# ECE_312_LAB_-_Diode_Temperture_Sensor.net
KiCad netlist of a schematic drawn in EAGLE
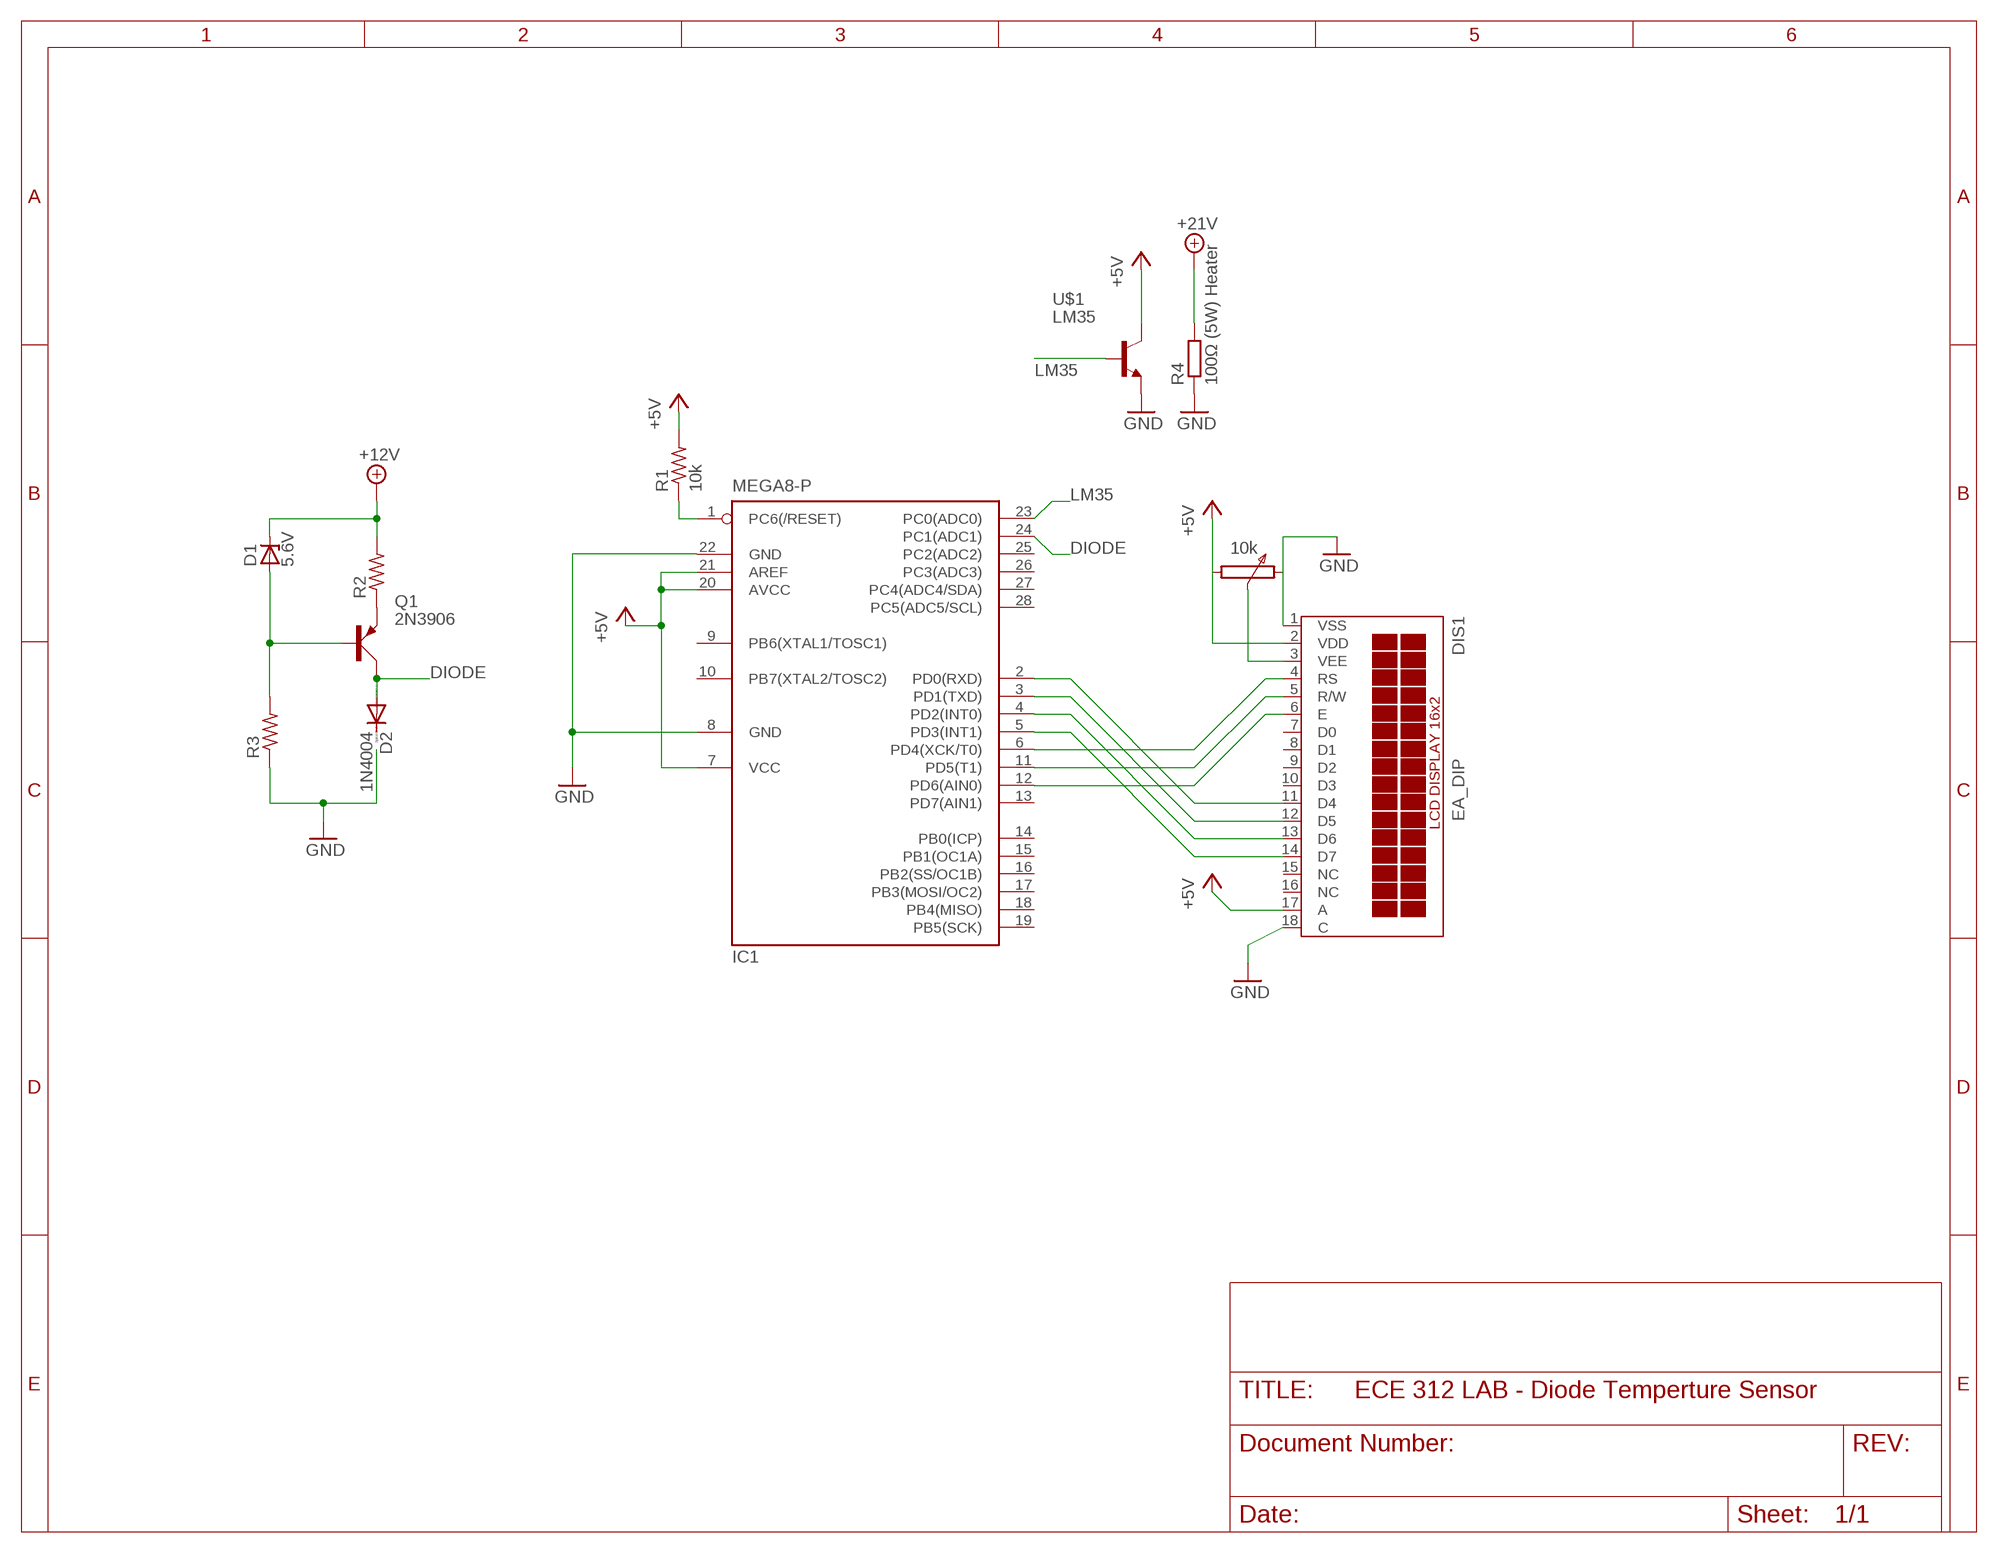
[diagram p0: schematic, sheet 1]

(export (version "E")
  (design (tool "Eeschema 10.0.6"))
  (components
    (comp (ref "D1")
      (value "5.6V")
      (footprint "eagle-import:C1702-15")
      (libsource (lib "eagle-import") (part "ZENER-DIODEC1702-15"))
    )
    (comp (ref "D2")
      (value "1N4004")
      (footprint "eagle-import:DO41-10")
      (libsource (lib "eagle-import") (part "1N4004"))
    )
    (comp (ref "DIS1")
      (value "EA_DIP")
      (footprint "eagle-import:EA_DIP")
      (libsource (lib "eagle-import") (part "EA_DIP"))
    )
    (comp (ref "IC1")
      (value "MEGA8-P")
      (footprint "eagle-import:DIL28-3")
      (libsource (lib "eagle-import") (part "MEGA8-P"))
    )
    (comp (ref "Q1")
      (value "2N3906")
      (footprint "eagle-import:TO92D")
      (libsource (lib "eagle-import") (part "2N3906"))
    )
    (comp (ref "R1")
      (value "10k")
      (footprint "eagle-import:0204V")
      (libsource (lib "eagle-import") (part "R-US_0204/2V"))
    )
    (comp (ref "R2")
      (value "R-US_0204/2V")
      (footprint "eagle-import:0204V")
      (libsource (lib "eagle-import") (part "R-US_0204/2V"))
    )
    (comp (ref "R3")
      (value "R-US_0204/2V")
      (footprint "eagle-import:0204V")
      (libsource (lib "eagle-import") (part "R-US_0204/2V"))
    )
    (comp (ref "R4")
      (value "100Ω (5W) Heater")
      (footprint "eagle-import:0204V")
      (libsource (lib "eagle-import") (part "R-EU_0204/2V"))
    )
    (comp (ref "U$1")
      (value "LM35")
      (footprint "eagle-import:TO220")
      (libsource (lib "eagle-import") (part "LM35"))
    )
  )
  (nets
    (net (code "1") (name "+5V") (class "Default")
      (node (ref "DIS1") (pin "17") (pinfunction "A_17") (pintype "passive"))
      (node (ref "DIS1") (pin "2") (pinfunction "VDD_2") (pintype "power_in"))
      (node (ref "IC1") (pin "20") (pinfunction "AVCC_20") (pintype "power_in"))
      (node (ref "IC1") (pin "21") (pinfunction "AREF_21") (pintype "passive"))
      (node (ref "IC1") (pin "7") (pinfunction "VCC_7") (pintype "power_in"))
      (node (ref "R1") (pin "2") (pinfunction "2_2") (pintype "passive"))
      (node (ref "U$1") (pin "2") (pinfunction "C_2") (pintype "passive"))
    )
    (net (code "2") (name "+12V") (class "Default")
      (node (ref "D1") (pin "C") (pinfunction "C_C") (pintype "passive"))
      (node (ref "R2") (pin "2") (pinfunction "2_2") (pintype "passive"))
    )
    (net (code "3") (name "+21V") (class "Default")
      (node (ref "R4") (pin "2") (pinfunction "2_2") (pintype "passive"))
    )
    (net (code "4") (name "/DIODE") (class "Default")
      (node (ref "D2") (pin "A") (pinfunction "A_A") (pintype "passive"))
      (node (ref "IC1") (pin "24") (pinfunction "PC1(ADC1)_24") (pintype "bidirectional"))
      (node (ref "Q1") (pin "C") (pinfunction "C_C") (pintype "passive"))
    )
    (net (code "5") (name "/LM35") (class "Default")
      (node (ref "IC1") (pin "23") (pinfunction "PC0(ADC0)_23") (pintype "bidirectional"))
      (node (ref "U$1") (pin "1") (pinfunction "B_1") (pintype "passive"))
    )
    (net (code "6") (name "GND") (class "Default")
      (node (ref "DIS1") (pin "1") (pinfunction "VSS_1") (pintype "power_in"))
      (node (ref "DIS1") (pin "18") (pinfunction "C_18") (pintype "passive"))
      (node (ref "IC1") (pin "22") (pinfunction "GND_22") (pintype "power_in"))
      (node (ref "IC1") (pin "8") (pinfunction "GND_8") (pintype "power_in"))
      (node (ref "R3") (pin "1") (pinfunction "1_1") (pintype "passive"))
      (node (ref "R4") (pin "1") (pinfunction "1_1") (pintype "passive"))
      (node (ref "U$1") (pin "3") (pinfunction "E_3") (pintype "passive"))
    )
    (net (code "7") (name "Net-(D1-PadA)") (class "Default")
      (node (ref "D1") (pin "A") (pinfunction "A_A") (pintype "passive"))
      (node (ref "Q1") (pin "B") (pinfunction "B_B") (pintype "passive"))
      (node (ref "R3") (pin "2") (pinfunction "2_2") (pintype "passive"))
    )
    (net (code "8") (name "Net-(DIS1-D4)") (class "Default")
      (node (ref "DIS1") (pin "11") (pinfunction "D4_11") (pintype "input"))
      (node (ref "IC1") (pin "2") (pinfunction "PD0(RXD)_2") (pintype "bidirectional"))
    )
    (net (code "9") (name "Net-(DIS1-D5)") (class "Default")
      (node (ref "DIS1") (pin "12") (pinfunction "D5_12") (pintype "input"))
      (node (ref "IC1") (pin "3") (pinfunction "PD1(TXD)_3") (pintype "bidirectional"))
    )
    (net (code "10") (name "Net-(DIS1-D6)") (class "Default")
      (node (ref "DIS1") (pin "13") (pinfunction "D6_13") (pintype "input"))
      (node (ref "IC1") (pin "4") (pinfunction "PD2(INT0)_4") (pintype "bidirectional"))
    )
    (net (code "11") (name "Net-(DIS1-D7)") (class "Default")
      (node (ref "DIS1") (pin "14") (pinfunction "D7_14") (pintype "input"))
      (node (ref "IC1") (pin "5") (pinfunction "PD3(INT1)_5") (pintype "bidirectional"))
    )
    (net (code "12") (name "Net-(DIS1-E)") (class "Default")
      (node (ref "DIS1") (pin "6") (pinfunction "E_6") (pintype "input"))
      (node (ref "IC1") (pin "12") (pinfunction "PD6(AIN0)_12") (pintype "bidirectional"))
    )
    (net (code "13") (name "Net-(DIS1-RS)") (class "Default")
      (node (ref "DIS1") (pin "4") (pinfunction "RS_4") (pintype "input"))
      (node (ref "IC1") (pin "6") (pinfunction "PD4(XCK/T0)_6") (pintype "bidirectional"))
    )
    (net (code "14") (name "Net-(DIS1-R{slash}W)") (class "Default")
      (node (ref "DIS1") (pin "5") (pinfunction "R/W_5") (pintype "input"))
      (node (ref "IC1") (pin "11") (pinfunction "PD5(T1)_11") (pintype "bidirectional"))
    )
    (net (code "15") (name "Net-(IC1-PC6({slash}RESET))") (class "Default")
      (node (ref "IC1") (pin "1") (pinfunction "PC6(/RESET)_1") (pintype "bidirectional"))
      (node (ref "R1") (pin "1") (pinfunction "1_1") (pintype "passive"))
    )
    (net (code "16") (name "Net-(Q1-PadE)") (class "Default")
      (node (ref "Q1") (pin "E") (pinfunction "E_E") (pintype "passive"))
      (node (ref "R2") (pin "1") (pinfunction "1_1") (pintype "passive"))
    )
    (net (code "17") (name "unconnected-(D2-PadC)") (class "Default")
      (node (ref "D2") (pin "C") (pinfunction "C_C") (pintype "passive"))
    )
    (net (code "18") (name "unconnected-(DIS1-D0-Pad7)") (class "Default")
      (node (ref "DIS1") (pin "7") (pinfunction "D0_7") (pintype "input"))
    )
    (net (code "19") (name "unconnected-(DIS1-D1-Pad8)") (class "Default")
      (node (ref "DIS1") (pin "8") (pinfunction "D1_8") (pintype "input"))
    )
    (net (code "20") (name "unconnected-(DIS1-D2-Pad9)") (class "Default")
      (node (ref "DIS1") (pin "9") (pinfunction "D2_9") (pintype "input"))
    )
    (net (code "21") (name "unconnected-(DIS1-D3-Pad10)") (class "Default")
      (node (ref "DIS1") (pin "10") (pinfunction "D3_10") (pintype "input"))
    )
    (net (code "22") (name "unconnected-(DIS1-NC-Pad15)") (class "Default")
      (node (ref "DIS1") (pin "15") (pinfunction "NC_15") (pintype "no_connect"))
    )
    (net (code "23") (name "unconnected-(DIS1-NC-Pad16)") (class "Default")
      (node (ref "DIS1") (pin "16") (pinfunction "NC_16") (pintype "no_connect"))
    )
    (net (code "24") (name "unconnected-(DIS1-VEE-Pad3)") (class "Default")
      (node (ref "DIS1") (pin "3") (pinfunction "VEE_3") (pintype "power_in"))
    )
    (net (code "25") (name "unconnected-(IC1-PB0(ICP)-Pad14)") (class "Default")
      (node (ref "IC1") (pin "14") (pinfunction "PB0(ICP)_14") (pintype "bidirectional"))
    )
    (net (code "26") (name "unconnected-(IC1-PB1(OC1A)-Pad15)") (class "Default")
      (node (ref "IC1") (pin "15") (pinfunction "PB1(OC1A)_15") (pintype "bidirectional"))
    )
    (net (code "27") (name "unconnected-(IC1-PB2(SS{slash}OC1B)-Pad16)") (class "Default")
      (node (ref "IC1") (pin "16") (pinfunction "PB2(SS/OC1B)_16") (pintype "bidirectional"))
    )
    (net (code "28") (name "unconnected-(IC1-PB3(MOSI{slash}OC2)-Pad17)") (class "Default")
      (node (ref "IC1") (pin "17") (pinfunction "PB3(MOSI/OC2)_17") (pintype "bidirectional"))
    )
    (net (code "29") (name "unconnected-(IC1-PB4(MISO)-Pad18)") (class "Default")
      (node (ref "IC1") (pin "18") (pinfunction "PB4(MISO)_18") (pintype "bidirectional"))
    )
    (net (code "30") (name "unconnected-(IC1-PB5(SCK)-Pad19)") (class "Default")
      (node (ref "IC1") (pin "19") (pinfunction "PB5(SCK)_19") (pintype "bidirectional"))
    )
    (net (code "31") (name "unconnected-(IC1-PB6(XTAL1{slash}TOSC1)-Pad9)") (class "Default")
      (node (ref "IC1") (pin "9") (pinfunction "PB6(XTAL1/TOSC1)_9") (pintype "bidirectional"))
    )
    (net (code "32") (name "unconnected-(IC1-PB7(XTAL2{slash}TOSC2)-Pad10)") (class "Default")
      (node (ref "IC1") (pin "10") (pinfunction "PB7(XTAL2/TOSC2)_10") (pintype "bidirectional"))
    )
    (net (code "33") (name "unconnected-(IC1-PC2(ADC2)-Pad25)") (class "Default")
      (node (ref "IC1") (pin "25") (pinfunction "PC2(ADC2)_25") (pintype "bidirectional"))
    )
    (net (code "34") (name "unconnected-(IC1-PC3(ADC3)-Pad26)") (class "Default")
      (node (ref "IC1") (pin "26") (pinfunction "PC3(ADC3)_26") (pintype "bidirectional"))
    )
    (net (code "35") (name "unconnected-(IC1-PC4(ADC4{slash}SDA)-Pad27)") (class "Default")
      (node (ref "IC1") (pin "27") (pinfunction "PC4(ADC4/SDA)_27") (pintype "bidirectional"))
    )
    (net (code "36") (name "unconnected-(IC1-PC5(ADC5{slash}SCL)-Pad28)") (class "Default")
      (node (ref "IC1") (pin "28") (pinfunction "PC5(ADC5/SCL)_28") (pintype "bidirectional"))
    )
    (net (code "37") (name "unconnected-(IC1-PD7(AIN1)-Pad13)") (class "Default")
      (node (ref "IC1") (pin "13") (pinfunction "PD7(AIN1)_13") (pintype "bidirectional"))
    )
  )
)
